# Project_Schematic.net
KiCad netlist of a schematic drawn in EAGLE
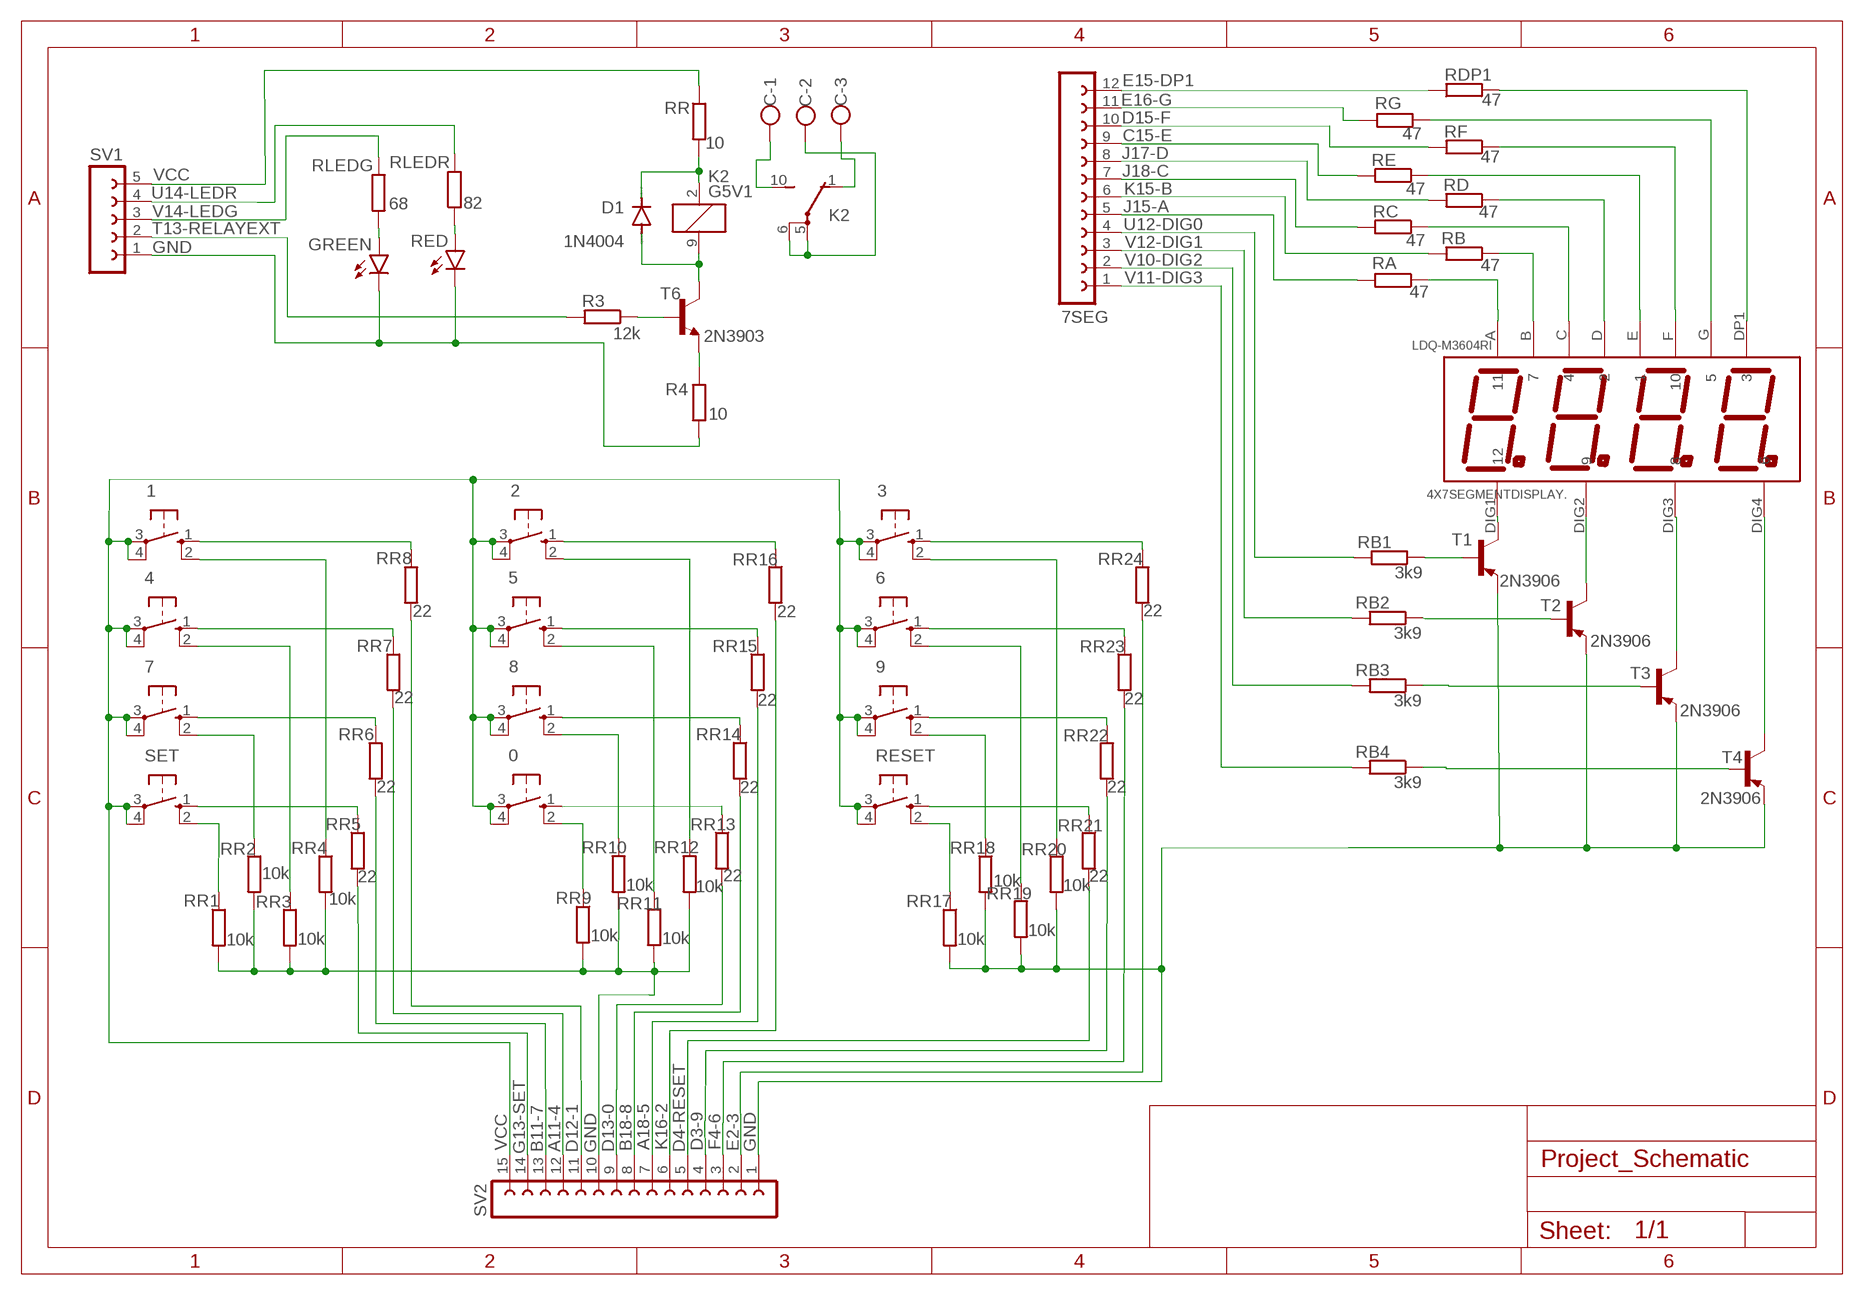
[diagram p0: schematic, sheet 1]

(export (version "E")
  (design (tool "Eeschema 10.0.6"))
  (components
    (comp (ref "0")
      (value "10-XX")
      (footprint "eagle-import:B3F-10XX")
      (fields (field (name "MPN") "B3F-1000"))
      (libsource (lib "eagle-import") (part "10-XX"))
    )
    (comp (ref "1")
      (value "10-XX")
      (footprint "eagle-import:B3F-10XX")
      (fields (field (name "MPN") "B3F-1000"))
      (libsource (lib "eagle-import") (part "10-XX"))
    )
    (comp (ref "2")
      (value "10-XX")
      (footprint "eagle-import:B3F-10XX")
      (fields (field (name "MPN") "B3F-1000"))
      (libsource (lib "eagle-import") (part "10-XX"))
    )
    (comp (ref "3")
      (value "10-XX")
      (footprint "eagle-import:B3F-10XX")
      (fields (field (name "MPN") "B3F-1000"))
      (libsource (lib "eagle-import") (part "10-XX"))
    )
    (comp (ref "4")
      (value "10-XX")
      (footprint "eagle-import:B3F-10XX")
      (fields (field (name "MPN") "B3F-1000"))
      (libsource (lib "eagle-import") (part "10-XX"))
    )
    (comp (ref "5")
      (value "10-XX")
      (footprint "eagle-import:B3F-10XX")
      (fields (field (name "MPN") "B3F-1000"))
      (libsource (lib "eagle-import") (part "10-XX"))
    )
    (comp (ref "6")
      (value "10-XX")
      (footprint "eagle-import:B3F-10XX")
      (fields (field (name "MPN") "B3F-1000"))
      (libsource (lib "eagle-import") (part "10-XX"))
    )
    (comp (ref "7")
      (value "10-XX")
      (footprint "eagle-import:B3F-10XX")
      (fields (field (name "MPN") "B3F-1000"))
      (libsource (lib "eagle-import") (part "10-XX"))
    )
    (comp (ref "7SEG")
      (value "FE12-1")
      (footprint "eagle-import:FE12")
      (libsource (lib "eagle-import") (part "FE12-1"))
    )
    (comp (ref "8")
      (value "10-XX")
      (footprint "eagle-import:B3F-10XX")
      (fields (field (name "MPN") "B3F-1000"))
      (libsource (lib "eagle-import") (part "10-XX"))
    )
    (comp (ref "9")
      (value "10-XX")
      (footprint "eagle-import:B3F-10XX")
      (fields (field (name "MPN") "B3F-1000"))
      (libsource (lib "eagle-import") (part "10-XX"))
    )
    (comp (ref "C")
      (value "W237-103")
      (footprint "eagle-import:W237-103")
      (fields (field (name "MPN") "237-103"))
      (libsource (lib "eagle-import") (part "W237-103"))
    )
    (comp (ref "D1")
      (value "1N4004")
      (footprint "eagle-import:DO41-10")
      (libsource (lib "eagle-import") (part "1N4004"))
    )
    (comp (ref "GREEN")
      (value "LED5MM")
      (footprint "eagle-import:LED5MM")
      (libsource (lib "eagle-import") (part "LED5MM"))
    )
    (comp (ref "K2")
      (value "G5V1")
      (footprint "eagle-import:G5V1")
      (fields (field (name "MPN") "G5V-1-DC24"))
      (libsource (lib "eagle-import") (part "G5V1"))
    )
    (comp (ref "LDQ-M3604RI")
      (value "4X7SEGMENTDISPLAY.")
      (footprint "eagle-import:4X7SCHEM")
      (libsource (lib "eagle-import") (part "4X7SEGMENTDISPLAY."))
    )
    (comp (ref "R3")
      (value "12k")
      (footprint "eagle-import:0207_10")
      (libsource (lib "eagle-import") (part "R-EU_0207/10"))
    )
    (comp (ref "R4")
      (value "10")
      (footprint "eagle-import:0207_10")
      (libsource (lib "eagle-import") (part "R-EU_0207/10"))
    )
    (comp (ref "RA")
      (value "47")
      (footprint "eagle-import:0207_10")
      (libsource (lib "eagle-import") (part "R-EU_0207/10"))
    )
    (comp (ref "RB")
      (value "47")
      (footprint "eagle-import:0207_10")
      (libsource (lib "eagle-import") (part "R-EU_0207/10"))
    )
    (comp (ref "RB1")
      (value "3k9")
      (footprint "eagle-import:0207_10")
      (libsource (lib "eagle-import") (part "R-EU_0207/10"))
    )
    (comp (ref "RB2")
      (value "3k9")
      (footprint "eagle-import:0207_10")
      (libsource (lib "eagle-import") (part "R-EU_0207/10"))
    )
    (comp (ref "RB3")
      (value "3k9")
      (footprint "eagle-import:0207_10")
      (libsource (lib "eagle-import") (part "R-EU_0207/10"))
    )
    (comp (ref "RB4")
      (value "3k9")
      (footprint "eagle-import:0207_10")
      (libsource (lib "eagle-import") (part "R-EU_0207/10"))
    )
    (comp (ref "RC")
      (value "47")
      (footprint "eagle-import:0207_10")
      (libsource (lib "eagle-import") (part "R-EU_0207/10"))
    )
    (comp (ref "RD")
      (value "47")
      (footprint "eagle-import:0207_10")
      (libsource (lib "eagle-import") (part "R-EU_0207/10"))
    )
    (comp (ref "RDP1")
      (value "47")
      (footprint "eagle-import:0207_10")
      (libsource (lib "eagle-import") (part "R-EU_0207/10"))
    )
    (comp (ref "RE")
      (value "47")
      (footprint "eagle-import:0207_10")
      (libsource (lib "eagle-import") (part "R-EU_0207/10"))
    )
    (comp (ref "RED")
      (value "LED5MM")
      (footprint "eagle-import:LED5MM")
      (libsource (lib "eagle-import") (part "LED5MM"))
    )
    (comp (ref "RESET")
      (value "10-XX")
      (footprint "eagle-import:B3F-10XX")
      (fields (field (name "MPN") "B3F-1000"))
      (libsource (lib "eagle-import") (part "10-XX"))
    )
    (comp (ref "RF")
      (value "47")
      (footprint "eagle-import:0207_10")
      (libsource (lib "eagle-import") (part "R-EU_0207/10"))
    )
    (comp (ref "RG")
      (value "47")
      (footprint "eagle-import:0207_10")
      (libsource (lib "eagle-import") (part "R-EU_0207/10"))
    )
    (comp (ref "RLEDG")
      (value "68")
      (footprint "eagle-import:0207_10")
      (libsource (lib "eagle-import") (part "R-EU_0207/10"))
    )
    (comp (ref "RLEDR")
      (value "82")
      (footprint "eagle-import:0207_10")
      (libsource (lib "eagle-import") (part "R-EU_0207/10"))
    )
    (comp (ref "RR")
      (value "10")
      (footprint "eagle-import:0207_10")
      (libsource (lib "eagle-import") (part "R-EU_0207/10"))
    )
    (comp (ref "RR1")
      (value "10k")
      (footprint "eagle-import:0207_10")
      (libsource (lib "eagle-import") (part "R-EU_0207/10"))
    )
    (comp (ref "RR2")
      (value "10k")
      (footprint "eagle-import:0207_10")
      (libsource (lib "eagle-import") (part "R-EU_0207/10"))
    )
    (comp (ref "RR3")
      (value "10k")
      (footprint "eagle-import:0207_10")
      (libsource (lib "eagle-import") (part "R-EU_0207/10"))
    )
    (comp (ref "RR4")
      (value "10k")
      (footprint "eagle-import:0207_10")
      (libsource (lib "eagle-import") (part "R-EU_0207/10"))
    )
    (comp (ref "RR5")
      (value "22")
      (footprint "eagle-import:0207_10")
      (libsource (lib "eagle-import") (part "R-EU_0207/10"))
    )
    (comp (ref "RR6")
      (value "22")
      (footprint "eagle-import:0207_10")
      (libsource (lib "eagle-import") (part "R-EU_0207/10"))
    )
    (comp (ref "RR7")
      (value "22")
      (footprint "eagle-import:0207_10")
      (libsource (lib "eagle-import") (part "R-EU_0207/10"))
    )
    (comp (ref "RR8")
      (value "22")
      (footprint "eagle-import:0207_10")
      (libsource (lib "eagle-import") (part "R-EU_0207/10"))
    )
    (comp (ref "RR9")
      (value "10k")
      (footprint "eagle-import:0207_10")
      (libsource (lib "eagle-import") (part "R-EU_0207/10"))
    )
    (comp (ref "RR10")
      (value "10k")
      (footprint "eagle-import:0207_10")
      (libsource (lib "eagle-import") (part "R-EU_0207/10"))
    )
    (comp (ref "RR11")
      (value "10k")
      (footprint "eagle-import:0207_10")
      (libsource (lib "eagle-import") (part "R-EU_0207/10"))
    )
    (comp (ref "RR12")
      (value "10k")
      (footprint "eagle-import:0207_10")
      (libsource (lib "eagle-import") (part "R-EU_0207/10"))
    )
    (comp (ref "RR13")
      (value "22")
      (footprint "eagle-import:0207_10")
      (libsource (lib "eagle-import") (part "R-EU_0207/10"))
    )
    (comp (ref "RR14")
      (value "22")
      (footprint "eagle-import:0207_10")
      (libsource (lib "eagle-import") (part "R-EU_0207/10"))
    )
    (comp (ref "RR15")
      (value "22")
      (footprint "eagle-import:0207_10")
      (libsource (lib "eagle-import") (part "R-EU_0207/10"))
    )
    (comp (ref "RR16")
      (value "22")
      (footprint "eagle-import:0207_10")
      (libsource (lib "eagle-import") (part "R-EU_0207/10"))
    )
    (comp (ref "RR17")
      (value "10k")
      (footprint "eagle-import:0207_10")
      (libsource (lib "eagle-import") (part "R-EU_0207/10"))
    )
    (comp (ref "RR18")
      (value "10k")
      (footprint "eagle-import:0207_10")
      (libsource (lib "eagle-import") (part "R-EU_0207/10"))
    )
    (comp (ref "RR19")
      (value "10k")
      (footprint "eagle-import:0207_10")
      (libsource (lib "eagle-import") (part "R-EU_0207/10"))
    )
    (comp (ref "RR20")
      (value "10k")
      (footprint "eagle-import:0207_10")
      (libsource (lib "eagle-import") (part "R-EU_0207/10"))
    )
    (comp (ref "RR21")
      (value "22")
      (footprint "eagle-import:0207_10")
      (libsource (lib "eagle-import") (part "R-EU_0207/10"))
    )
    (comp (ref "RR22")
      (value "22")
      (footprint "eagle-import:0207_10")
      (libsource (lib "eagle-import") (part "R-EU_0207/10"))
    )
    (comp (ref "RR23")
      (value "22")
      (footprint "eagle-import:0207_10")
      (libsource (lib "eagle-import") (part "R-EU_0207/10"))
    )
    (comp (ref "RR24")
      (value "22")
      (footprint "eagle-import:0207_10")
      (libsource (lib "eagle-import") (part "R-EU_0207/10"))
    )
    (comp (ref "SET")
      (value "10-XX")
      (footprint "eagle-import:B3F-10XX")
      (fields (field (name "MPN") "B3F-1000"))
      (libsource (lib "eagle-import") (part "10-XX"))
    )
    (comp (ref "SV1")
      (value "FE05-1")
      (footprint "eagle-import:FE05-1")
      (libsource (lib "eagle-import") (part "FE05-1"))
    )
    (comp (ref "SV2")
      (value "FE15-1")
      (footprint "eagle-import:FE15")
      (libsource (lib "eagle-import") (part "FE15-1"))
    )
    (comp (ref "T1")
      (value "2N3906")
      (footprint "eagle-import:TO92-EBC")
      (libsource (lib "eagle-import") (part "-PNP-TO92-EBC2N3906"))
    )
    (comp (ref "T2")
      (value "2N3906")
      (footprint "eagle-import:TO92-EBC")
      (libsource (lib "eagle-import") (part "-PNP-TO92-EBC2N3906"))
    )
    (comp (ref "T3")
      (value "2N3906")
      (footprint "eagle-import:TO92-EBC")
      (libsource (lib "eagle-import") (part "-PNP-TO92-EBC2N3906"))
    )
    (comp (ref "T4")
      (value "2N3906")
      (footprint "eagle-import:TO92-EBC")
      (libsource (lib "eagle-import") (part "-PNP-TO92-EBC2N3906"))
    )
    (comp (ref "T6")
      (value "2N3903")
      (footprint "eagle-import:TO92-EBC")
      (libsource (lib "eagle-import") (part "-NPN-TO92-EBC2N3903"))
    )
  )
  (nets
    (net (code "1") (name "/A11-4") (class "Default")
      (node (ref "RR7") (pin "2") (pinfunction "2_2") (pintype "passive"))
      (node (ref "SV2") (pin "12") (pinfunction "12_12") (pintype "passive"))
    )
    (net (code "2") (name "/A18-5") (class "Default")
      (node (ref "RR15") (pin "2") (pinfunction "2_2") (pintype "passive"))
      (node (ref "SV2") (pin "7") (pinfunction "7_7") (pintype "passive"))
    )
    (net (code "3") (name "/B11-7") (class "Default")
      (node (ref "RR6") (pin "2") (pinfunction "2_2") (pintype "passive"))
      (node (ref "SV2") (pin "13") (pinfunction "13_13") (pintype "passive"))
    )
    (net (code "4") (name "/B18-8") (class "Default")
      (node (ref "RR14") (pin "2") (pinfunction "2_2") (pintype "passive"))
      (node (ref "SV2") (pin "8") (pinfunction "8_8") (pintype "passive"))
    )
    (net (code "5") (name "/C15-E") (class "Default")
      (node (ref "7SEG") (pin "9") (pinfunction "9_9") (pintype "passive"))
      (node (ref "RE") (pin "2") (pinfunction "2_2") (pintype "passive"))
    )
    (net (code "6") (name "/D3-9") (class "Default")
      (node (ref "RR22") (pin "2") (pinfunction "2_2") (pintype "passive"))
      (node (ref "SV2") (pin "4") (pinfunction "4_4") (pintype "passive"))
    )
    (net (code "7") (name "/D4-RESET") (class "Default")
      (node (ref "RR21") (pin "2") (pinfunction "2_2") (pintype "passive"))
      (node (ref "SV2") (pin "5") (pinfunction "5_5") (pintype "passive"))
    )
    (net (code "8") (name "/D12-1") (class "Default")
      (node (ref "RR8") (pin "2") (pinfunction "2_2") (pintype "passive"))
      (node (ref "SV2") (pin "11") (pinfunction "11_11") (pintype "passive"))
    )
    (net (code "9") (name "/D13-0") (class "Default")
      (node (ref "RR13") (pin "2") (pinfunction "2_2") (pintype "passive"))
      (node (ref "SV2") (pin "9") (pinfunction "9_9") (pintype "passive"))
    )
    (net (code "10") (name "/D15-F") (class "Default")
      (node (ref "7SEG") (pin "10") (pinfunction "10_10") (pintype "passive"))
      (node (ref "RF") (pin "2") (pinfunction "2_2") (pintype "passive"))
    )
    (net (code "11") (name "/E2-3") (class "Default")
      (node (ref "RR24") (pin "2") (pinfunction "2_2") (pintype "passive"))
      (node (ref "SV2") (pin "2") (pinfunction "2_2") (pintype "passive"))
    )
    (net (code "12") (name "/E15-DP1") (class "Default")
      (node (ref "7SEG") (pin "12") (pinfunction "12_12") (pintype "passive"))
      (node (ref "RDP1") (pin "1") (pinfunction "1_1") (pintype "passive"))
    )
    (net (code "13") (name "/E16-G") (class "Default")
      (node (ref "7SEG") (pin "11") (pinfunction "11_11") (pintype "passive"))
      (node (ref "RG") (pin "2") (pinfunction "2_2") (pintype "passive"))
    )
    (net (code "14") (name "/F4-6") (class "Default")
      (node (ref "RR23") (pin "2") (pinfunction "2_2") (pintype "passive"))
      (node (ref "SV2") (pin "3") (pinfunction "3_3") (pintype "passive"))
    )
    (net (code "15") (name "/G13-SET") (class "Default")
      (node (ref "RR5") (pin "2") (pinfunction "2_2") (pintype "passive"))
      (node (ref "SV2") (pin "14") (pinfunction "14_14") (pintype "passive"))
    )
    (net (code "16") (name "/GND") (class "Default")
      (node (ref "GREEN") (pin "K") (pinfunction "C_K") (pintype "passive"))
      (node (ref "R4") (pin "2") (pinfunction "2_2") (pintype "passive"))
      (node (ref "RED") (pin "K") (pinfunction "C_K") (pintype "passive"))
      (node (ref "RR1") (pin "2") (pinfunction "2_2") (pintype "passive"))
      (node (ref "RR10") (pin "2") (pinfunction "2_2") (pintype "passive"))
      (node (ref "RR11") (pin "2") (pinfunction "2_2") (pintype "passive"))
      (node (ref "RR12") (pin "2") (pinfunction "2_2") (pintype "passive"))
      (node (ref "RR17") (pin "2") (pinfunction "2_2") (pintype "passive"))
      (node (ref "RR18") (pin "2") (pinfunction "2_2") (pintype "passive"))
      (node (ref "RR19") (pin "2") (pinfunction "2_2") (pintype "passive"))
      (node (ref "RR2") (pin "2") (pinfunction "2_2") (pintype "passive"))
      (node (ref "RR20") (pin "2") (pinfunction "2_2") (pintype "passive"))
      (node (ref "RR3") (pin "2") (pinfunction "2_2") (pintype "passive"))
      (node (ref "RR4") (pin "2") (pinfunction "2_2") (pintype "passive"))
      (node (ref "RR9") (pin "2") (pinfunction "2_2") (pintype "passive"))
      (node (ref "SV1") (pin "1") (pinfunction "1_1") (pintype "passive"))
      (node (ref "SV2") (pin "1") (pinfunction "1_1") (pintype "passive"))
      (node (ref "SV2") (pin "10") (pinfunction "10_10") (pintype "passive"))
      (node (ref "T1") (pin "E") (pinfunction "E_E") (pintype "passive"))
      (node (ref "T2") (pin "E") (pinfunction "E_E") (pintype "passive"))
      (node (ref "T3") (pin "E") (pinfunction "E_E") (pintype "passive"))
      (node (ref "T4") (pin "E") (pinfunction "E_E") (pintype "passive"))
    )
    (net (code "17") (name "/J15-A") (class "Default")
      (node (ref "7SEG") (pin "5") (pinfunction "5_5") (pintype "passive"))
      (node (ref "RA") (pin "2") (pinfunction "2_2") (pintype "passive"))
    )
    (net (code "18") (name "/J17-D") (class "Default")
      (node (ref "7SEG") (pin "8") (pinfunction "8_8") (pintype "passive"))
      (node (ref "RD") (pin "2") (pinfunction "2_2") (pintype "passive"))
    )
    (net (code "19") (name "/J18-C") (class "Default")
      (node (ref "7SEG") (pin "7") (pinfunction "7_7") (pintype "passive"))
      (node (ref "RC") (pin "2") (pinfunction "2_2") (pintype "passive"))
    )
    (net (code "20") (name "/K15-B") (class "Default")
      (node (ref "7SEG") (pin "6") (pinfunction "6_6") (pintype "passive"))
      (node (ref "RB") (pin "2") (pinfunction "2_2") (pintype "passive"))
    )
    (net (code "21") (name "/K16-2") (class "Default")
      (node (ref "RR16") (pin "2") (pinfunction "2_2") (pintype "passive"))
      (node (ref "SV2") (pin "6") (pinfunction "6_6") (pintype "passive"))
    )
    (net (code "22") (name "/T13-RELAYEXT") (class "Default")
      (node (ref "R3") (pin "2") (pinfunction "2_2") (pintype "passive"))
      (node (ref "SV1") (pin "2") (pinfunction "2_2") (pintype "passive"))
    )
    (net (code "23") (name "/U12-DIG0") (class "Default")
      (node (ref "7SEG") (pin "4") (pinfunction "4_4") (pintype "passive"))
      (node (ref "RB1") (pin "2") (pinfunction "2_2") (pintype "passive"))
    )
    (net (code "24") (name "/U14-LEDR") (class "Default")
      (node (ref "RLEDR") (pin "2") (pinfunction "2_2") (pintype "passive"))
      (node (ref "SV1") (pin "4") (pinfunction "4_4") (pintype "passive"))
    )
    (net (code "25") (name "/V10-DIG2") (class "Default")
      (node (ref "7SEG") (pin "2") (pinfunction "2_2") (pintype "passive"))
      (node (ref "RB3") (pin "2") (pinfunction "2_2") (pintype "passive"))
    )
    (net (code "26") (name "/V11-DIG3") (class "Default")
      (node (ref "7SEG") (pin "1") (pinfunction "1_1") (pintype "passive"))
      (node (ref "RB4") (pin "2") (pinfunction "2_2") (pintype "passive"))
    )
    (net (code "27") (name "/V12-DIG1") (class "Default")
      (node (ref "7SEG") (pin "3") (pinfunction "3_3") (pintype "passive"))
      (node (ref "RB2") (pin "2") (pinfunction "2_2") (pintype "passive"))
    )
    (net (code "28") (name "/V14-LEDG") (class "Default")
      (node (ref "RLEDG") (pin "1") (pinfunction "1_1") (pintype "passive"))
      (node (ref "SV1") (pin "3") (pinfunction "3_3") (pintype "passive"))
    )
    (net (code "29") (name "/VCC") (class "Default")
      (node (ref "1") (pin "3") (pinfunction "P_3") (pintype "passive"))
      (node (ref "1") (pin "4") (pinfunction "P1_4") (pintype "passive"))
      (node (ref "3") (pin "3") (pinfunction "P_3") (pintype "passive"))
      (node (ref "3") (pin "4") (pinfunction "P1_4") (pintype "passive"))
      (node (ref "4") (pin "3") (pinfunction "P_3") (pintype "passive"))
      (node (ref "4") (pin "4") (pinfunction "P1_4") (pintype "passive"))
      (node (ref "6") (pin "3") (pinfunction "P_3") (pintype "passive"))
      (node (ref "6") (pin "4") (pinfunction "P1_4") (pintype "passive"))
      (node (ref "7") (pin "3") (pinfunction "P_3") (pintype "passive"))
      (node (ref "7") (pin "4") (pinfunction "P1_4") (pintype "passive"))
      (node (ref "9") (pin "3") (pinfunction "P_3") (pintype "passive"))
      (node (ref "9") (pin "4") (pinfunction "P1_4") (pintype "passive"))
      (node (ref "RESET") (pin "3") (pinfunction "P_3") (pintype "passive"))
      (node (ref "RESET") (pin "4") (pinfunction "P1_4") (pintype "passive"))
      (node (ref "RR") (pin "1") (pinfunction "1_1") (pintype "passive"))
      (node (ref "SET") (pin "3") (pinfunction "P_3") (pintype "passive"))
      (node (ref "SET") (pin "4") (pinfunction "P1_4") (pintype "passive"))
      (node (ref "SV1") (pin "5") (pinfunction "5_5") (pintype "passive"))
      (node (ref "SV2") (pin "15") (pinfunction "15_15") (pintype "passive"))
    )
    (net (code "30") (name "Net-(0-P)") (class "Default")
      (node (ref "0") (pin "3") (pinfunction "P_3") (pintype "passive"))
      (node (ref "0") (pin "4") (pinfunction "P1_4") (pintype "passive"))
      (node (ref "2") (pin "3") (pinfunction "P_3") (pintype "passive"))
      (node (ref "2") (pin "4") (pinfunction "P1_4") (pintype "passive"))
      (node (ref "5") (pin "3") (pinfunction "P_3") (pintype "passive"))
      (node (ref "5") (pin "4") (pinfunction "P1_4") (pintype "passive"))
      (node (ref "8") (pin "3") (pinfunction "P_3") (pintype "passive"))
      (node (ref "8") (pin "4") (pinfunction "P1_4") (pintype "passive"))
    )
    (net (code "31") (name "Net-(0-S)") (class "Default")
      (node (ref "0") (pin "1") (pinfunction "S_1") (pintype "passive"))
      (node (ref "RR13") (pin "1") (pinfunction "1_1") (pintype "passive"))
    )
    (net (code "32") (name "Net-(0-S1)") (class "Default")
      (node (ref "0") (pin "2") (pinfunction "S1_2") (pintype "passive"))
      (node (ref "RR9") (pin "1") (pinfunction "1_1") (pintype "passive"))
    )
    (net (code "33") (name "Net-(1-S)") (class "Default")
      (node (ref "1") (pin "1") (pinfunction "S_1") (pintype "passive"))
      (node (ref "RR8") (pin "1") (pinfunction "1_1") (pintype "passive"))
    )
    (net (code "34") (name "Net-(1-S1)") (class "Default")
      (node (ref "1") (pin "2") (pinfunction "S1_2") (pintype "passive"))
      (node (ref "RR4") (pin "1") (pinfunction "1_1") (pintype "passive"))
    )
    (net (code "35") (name "Net-(2-S)") (class "Default")
      (node (ref "2") (pin "1") (pinfunction "S_1") (pintype "passive"))
      (node (ref "RR16") (pin "1") (pinfunction "1_1") (pintype "passive"))
    )
    (net (code "36") (name "Net-(2-S1)") (class "Default")
      (node (ref "2") (pin "2") (pinfunction "S1_2") (pintype "passive"))
      (node (ref "RR12") (pin "1") (pinfunction "1_1") (pintype "passive"))
    )
    (net (code "37") (name "Net-(3-S)") (class "Default")
      (node (ref "3") (pin "1") (pinfunction "S_1") (pintype "passive"))
      (node (ref "RR24") (pin "1") (pinfunction "1_1") (pintype "passive"))
    )
    (net (code "38") (name "Net-(3-S1)") (class "Default")
      (node (ref "3") (pin "2") (pinfunction "S1_2") (pintype "passive"))
      (node (ref "RR20") (pin "1") (pinfunction "1_1") (pintype "passive"))
    )
    (net (code "39") (name "Net-(4-S)") (class "Default")
      (node (ref "4") (pin "1") (pinfunction "S_1") (pintype "passive"))
      (node (ref "RR7") (pin "1") (pinfunction "1_1") (pintype "passive"))
    )
    (net (code "40") (name "Net-(4-S1)") (class "Default")
      (node (ref "4") (pin "2") (pinfunction "S1_2") (pintype "passive"))
      (node (ref "RR3") (pin "1") (pinfunction "1_1") (pintype "passive"))
    )
    (net (code "41") (name "Net-(5-S)") (class "Default")
      (node (ref "5") (pin "1") (pinfunction "S_1") (pintype "passive"))
      (node (ref "RR15") (pin "1") (pinfunction "1_1") (pintype "passive"))
    )
    (net (code "42") (name "Net-(5-S1)") (class "Default")
      (node (ref "5") (pin "2") (pinfunction "S1_2") (pintype "passive"))
      (node (ref "RR11") (pin "1") (pinfunction "1_1") (pintype "passive"))
    )
    (net (code "43") (name "Net-(6-S)") (class "Default")
      (node (ref "6") (pin "1") (pinfunction "S_1") (pintype "passive"))
      (node (ref "RR23") (pin "1") (pinfunction "1_1") (pintype "passive"))
    )
    (net (code "44") (name "Net-(6-S1)") (class "Default")
      (node (ref "6") (pin "2") (pinfunction "S1_2") (pintype "passive"))
      (node (ref "RR19") (pin "1") (pinfunction "1_1") (pintype "passive"))
    )
    (net (code "45") (name "Net-(7-S)") (class "Default")
      (node (ref "7") (pin "1") (pinfunction "S_1") (pintype "passive"))
      (node (ref "RR6") (pin "1") (pinfunction "1_1") (pintype "passive"))
    )
    (net (code "46") (name "Net-(7-S1)") (class "Default")
      (node (ref "7") (pin "2") (pinfunction "S1_2") (pintype "passive"))
      (node (ref "RR2") (pin "1") (pinfunction "1_1") (pintype "passive"))
    )
    (net (code "47") (name "Net-(8-S)") (class "Default")
      (node (ref "8") (pin "1") (pinfunction "S_1") (pintype "passive"))
      (node (ref "RR14") (pin "1") (pinfunction "1_1") (pintype "passive"))
    )
    (net (code "48") (name "Net-(8-S1)") (class "Default")
      (node (ref "8") (pin "2") (pinfunction "S1_2") (pintype "passive"))
      (node (ref "RR10") (pin "1") (pinfunction "1_1") (pintype "passive"))
    )
    (net (code "49") (name "Net-(9-S)") (class "Default")
      (node (ref "9") (pin "1") (pinfunction "S_1") (pintype "passive"))
      (node (ref "RR22") (pin "1") (pinfunction "1_1") (pintype "passive"))
    )
    (net (code "50") (name "Net-(9-S1)") (class "Default")
      (node (ref "9") (pin "2") (pinfunction "S1_2") (pintype "passive"))
      (node (ref "RR18") (pin "1") (pinfunction "1_1") (pintype "passive"))
    )
    (net (code "51") (name "Net-(CA-KL)") (class "Default")
      (node (ref "C") (pin "1") (pinfunction "KL_1") (pintype "passive"))
      (node (ref "K2") (pin "10") (pinfunction "S_10") (pintype "passive"))
    )
    (net (code "52") (name "Net-(CB-KL)") (class "Default")
      (node (ref "C") (pin "2") (pinfunction "KL_2") (pintype "passive"))
      (node (ref "K2") (pin "5") (pinfunction "P_5") (pintype "passive"))
      (node (ref "K2") (pin "6") (pinfunction "P_6") (pintype "passive"))
    )
    (net (code "53") (name "Net-(CC-KL)") (class "Default")
      (node (ref "C") (pin "3") (pinfunction "KL_3") (pintype "passive"))
      (node (ref "K2") (pin "1") (pinfunction "O_1") (pintype "passive"))
    )
    (net (code "54") (name "Net-(GREEN-PadA)") (class "Default")
      (node (ref "GREEN") (pin "A") (pinfunction "A_A") (pintype "passive"))
      (node (ref "RLEDG") (pin "2") (pinfunction "2_2") (pintype "passive"))
    )
    (net (code "55") (name "Net-(K2A-1)") (class "Default")
      (node (ref "D1") (pin "C") (pinfunction "C_C") (pintype "passive"))
      (node (ref "K2") (pin "2") (pinfunction "1_2") (pintype "passive"))
      (node (ref "RR") (pin "2") (pinfunction "2_2") (pintype "passive"))
    )
    (net (code "56") (name "Net-(K2A-2)") (class "Default")
      (node (ref "D1") (pin "A") (pinfunction "A_A") (pintype "passive"))
      (node (ref "K2") (pin "9") (pinfunction "2_9") (pintype "passive"))
      (node (ref "T6") (pin "C") (pinfunction "C_C") (pintype "passive"))
    )
    (net (code "57") (name "Net-(LDQ-M3604RI-1)") (class "Default")
      (node (ref "LDQ-M3604RI") (pin "E") (pinfunction "1_E") (pintype "bidirectional"))
      (node (ref "RE") (pin "1") (pinfunction "1_1") (pintype "passive"))
    )
    (net (code "58") (name "Net-(LDQ-M3604RI-2)") (class "Default")
      (node (ref "LDQ-M3604RI") (pin "D") (pinfunction "2_D") (pintype "bidirectional"))
      (node (ref "RD") (pin "1") (pinfunction "1_1") (pintype "passive"))
    )
    (net (code "59") (name "Net-(LDQ-M3604RI-3)") (class "Default")
      (node (ref "LDQ-M3604RI") (pin "DP1") (pinfunction "3_DP1") (pintype "bidirectional"))
      (node (ref "RDP1") (pin "2") (pinfunction "2_2") (pintype "passive"))
    )
    (net (code "60") (name "Net-(LDQ-M3604RI-4)") (class "Default")
      (node (ref "LDQ-M3604RI") (pin "C") (pinfunction "4_C") (pintype "bidirectional"))
      (node (ref "RC") (pin "1") (pinfunction "1_1") (pintype "passive"))
    )
    (net (code "61") (name "Net-(LDQ-M3604RI-5)") (class "Default")
      (node (ref "LDQ-M3604RI") (pin "G") (pinfunction "5_G") (pintype "bidirectional"))
      (node (ref "RG") (pin "1") (pinfunction "1_1") (pintype "passive"))
    )
    (net (code "62") (name "Net-(LDQ-M3604RI-6)") (class "Default")
      (node (ref "LDQ-M3604RI") (pin "DIG4") (pinfunction "6_DIG4") (pintype "bidirectional"))
      (node (ref "T4") (pin "C") (pinfunction "C_C") (pintype "passive"))
    )
    (net (code "63") (name "Net-(LDQ-M3604RI-7)") (class "Default")
      (node (ref "LDQ-M3604RI") (pin "B") (pinfunction "7_B") (pintype "bidirectional"))
      (node (ref "RB") (pin "1") (pinfunction "1_1") (pintype "passive"))
    )
    (net (code "64") (name "Net-(LDQ-M3604RI-8)") (class "Default")
      (node (ref "LDQ-M3604RI") (pin "DIG3") (pinfunction "8_DIG3") (pintype "bidirectional"))
      (node (ref "T3") (pin "C") (pinfunction "C_C") (pintype "passive"))
    )
    (net (code "65") (name "Net-(LDQ-M3604RI-9)") (class "Default")
      (node (ref "LDQ-M3604RI") (pin "DIG2") (pinfunction "9_DIG2") (pintype "bidirectional"))
      (node (ref "T2") (pin "C") (pinfunction "C_C") (pintype "passive"))
    )
    (net (code "66") (name "Net-(LDQ-M3604RI-10)") (class "Default")
      (node (ref "LDQ-M3604RI") (pin "F") (pinfunction "10_F") (pintype "bidirectional"))
      (node (ref "RF") (pin "1") (pinfunction "1_1") (pintype "passive"))
    )
    (net (code "67") (name "Net-(LDQ-M3604RI-11)") (class "Default")
      (node (ref "LDQ-M3604RI") (pin "A") (pinfunction "11_A") (pintype "bidirectional"))
      (node (ref "RA") (pin "1") (pinfunction "1_1") (pintype "passive"))
    )
    (net (code "68") (name "Net-(LDQ-M3604RI-12)") (class "Default")
      (node (ref "LDQ-M3604RI") (pin "DIG1") (pinfunction "12_DIG1") (pintype "bidirectional"))
      (node (ref "T1") (pin "C") (pinfunction "C_C") (pintype "passive"))
    )
    (net (code "69") (name "Net-(R3-Pad1)") (class "Default")
      (node (ref "R3") (pin "1") (pinfunction "1_1") (pintype "passive"))
      (node (ref "T6") (pin "B") (pinfunction "B_B") (pintype "passive"))
    )
    (net (code "70") (name "Net-(R4-Pad1)") (class "Default")
      (node (ref "R4") (pin "1") (pinfunction "1_1") (pintype "passive"))
      (node (ref "T6") (pin "E") (pinfunction "E_E") (pintype "passive"))
    )
    (net (code "71") (name "Net-(RB1-Pad1)") (class "Default")
      (node (ref "RB1") (pin "1") (pinfunction "1_1") (pintype "passive"))
      (node (ref "T1") (pin "B") (pinfunction "B_B") (pintype "passive"))
    )
    (net (code "72") (name "Net-(RB2-Pad1)") (class "Default")
      (node (ref "RB2") (pin "1") (pinfunction "1_1") (pintype "passive"))
      (node (ref "T2") (pin "B") (pinfunction "B_B") (pintype "passive"))
    )
    (net (code "73") (name "Net-(RB3-Pad1)") (class "Default")
      (node (ref "RB3") (pin "1") (pinfunction "1_1") (pintype "passive"))
      (node (ref "T3") (pin "B") (pinfunction "B_B") (pintype "passive"))
    )
    (net (code "74") (name "Net-(RB4-Pad1)") (class "Default")
      (node (ref "RB4") (pin "1") (pinfunction "1_1") (pintype "passive"))
      (node (ref "T4") (pin "B") (pinfunction "B_B") (pintype "passive"))
    )
    (net (code "75") (name "Net-(RED-PadA)") (class "Default")
      (node (ref "RED") (pin "A") (pinfunction "A_A") (pintype "passive"))
      (node (ref "RLEDR") (pin "1") (pinfunction "1_1") (pintype "passive"))
    )
    (net (code "76") (name "Net-(RESET-S)") (class "Default")
      (node (ref "RESET") (pin "1") (pinfunction "S_1") (pintype "passive"))
      (node (ref "RR21") (pin "1") (pinfunction "1_1") (pintype "passive"))
    )
    (net (code "77") (name "Net-(RESET-S1)") (class "Default")
      (node (ref "RESET") (pin "2") (pinfunction "S1_2") (pintype "passive"))
      (node (ref "RR17") (pin "1") (pinfunction "1_1") (pintype "passive"))
    )
    (net (code "78") (name "Net-(SET-S)") (class "Default")
      (node (ref "RR5") (pin "1") (pinfunction "1_1") (pintype "passive"))
      (node (ref "SET") (pin "1") (pinfunction "S_1") (pintype "passive"))
    )
    (net (code "79") (name "Net-(SET-S1)") (class "Default")
      (node (ref "RR1") (pin "1") (pinfunction "1_1") (pintype "passive"))
      (node (ref "SET") (pin "2") (pinfunction "S1_2") (pintype "passive"))
    )
  )
)
